# SOM_Power.net
KiCad netlist of a schematic drawn in Altium Designer
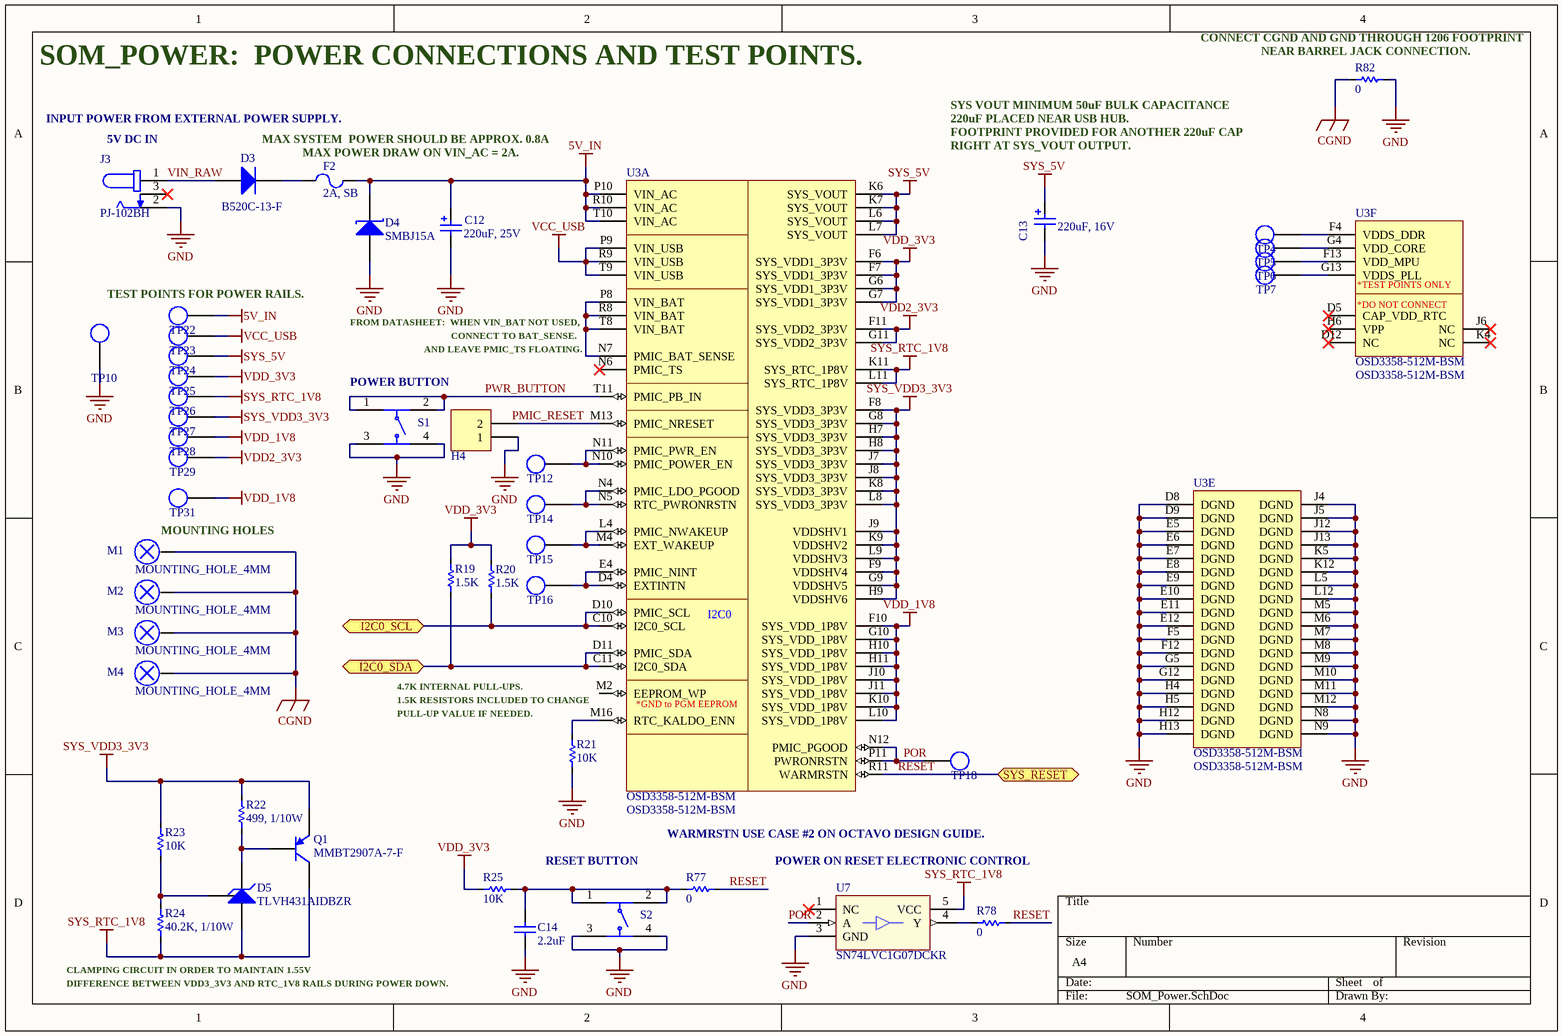
[diagram p0: SOM_Power.SchDoc]

(export (version "E")
  (design (tool "Eeschema 10.0.6"))
  (components
    (comp (ref "C12")
      (value "220uF, 25V")
      (footprint "CAP_SMD_6.3x7.7")
      (description "CAP ALUM 220UF 20% 25V SMD")
      (fields
        (field (name "MANUFACTURER PART NO.") "UCM1E221MCL1GS")
        (field (name "MANUFACTURER") "Nichicon")
      )
      (libsource (lib "OSD335-X_Devboard") (part "UCM1E221MCL1GS"))
    )
    (comp (ref "C13")
      (value "220uF, 16V")
      (footprint "CAP_SMD_6.3x7.7")
      (description "CAP 220 UF 20% 16 V")
      (fields
        (field (name "MANUFACTURER PART NO.") "865080345012")
        (field (name "MANUFACTURER") "Wurth Elektronik")
      )
      (libsource (lib "OSD335-X_Devboard") (part "865080345012"))
    )
    (comp (ref "C14")
      (value "2.2uF")
      (footprint "CAP_0603")
      (description "CAP CER 2.2UF 16V X5R 0603")
      (fields (field (name "MANUFACTURER") "KEMET") (field (name "MANUFACTURER PART NO.") "C0603C104M4RACTU"))
      (libsource (lib "OSD335-X_Devboard") (part "C0603C225M4PAC7867"))
    )
    (comp (ref "D3")
      (value "B520C-13-F")
      (footprint "D0-214AA")
      (description "DIODE SCHOTTKY 20V 5A SMC")
      (fields (field (name "MANUFACTURER") "Diodes Incorporated"))
      (libsource (lib "OSD335-X_Devboard") (part "B520C-13-F"))
    )
    (comp (ref "D4")
      (value "SMBJ15A")
      (footprint "D0-214AA")
      (description "TVS DIODE 15V 24.4V DO214AA")
      (fields (field (name "MANUFACTURER") "Littelfuse Inc."))
      (libsource (lib "OSD335-X_Devboard") (part "SMBJ15A"))
    )
    (comp (ref "D5")
      (value "TLVH431AIDBZR")
      (footprint "SOT-23-3")
      (description "IC VREF SHUNT 18V 1% SOT23-3")
      (fields (field (name "MANUFACTURER") "Texas Instruments"))
      (libsource (lib "OSD335-X_Devboard") (part "TLVH431AIDBZR"))
    )
    (comp (ref "F2")
      (value "2A, SB")
      (footprint "CAP_0603")
      (description "FUSE BOARD MOUNT 2A 32VDC 0603")
      (fields
        (field (name "MANUFACTURER") "Bourns Inc.")
        (field (name "MANUFACTURER PART NO.") "SF-0603S200-2")
      )
      (libsource (lib "OSD335-X_Devboard") (part "SF-0603S200-2"))
    )
    (comp (ref "H4")
      (value "02p")
      (footprint "HEADER_2X1_2.54MM")
      (description "CONN HEADER VERT 2POS 2.54MM")
      (fields
        (field (name "MANUFACTURER") "Wurth Elektronik")
        (field (name "MANUFACTURER PART NO.") "61300211121")
      )
      (libsource (lib "OSD335-X_Devboard") (part "61300211121"))
    )
    (comp (ref "J3")
      (value "PJ-102BH")
      (footprint "PJ-102BH")
      (description "CONN PWR JACK 2.5X5.5MM SOLDER")
      (fields (field (name "MANUFACTURER") "CUI Devices"))
      (libsource (lib "OSD335-X_Devboard") (part "PJ-102BH"))
    )
    (comp (ref "M1")
      (value "MOUNTING_HOLE_4MM")
      (footprint "MOUNTING_HOLE_4MM")
      (libsource (lib "OSD335-X_Devboard") (part "MOUNTING_HOLE_4MM"))
    )
    (comp (ref "M2")
      (value "MOUNTING_HOLE_4MM")
      (footprint "MOUNTING_HOLE_4MM")
      (libsource (lib "OSD335-X_Devboard") (part "MOUNTING_HOLE_4MM"))
    )
    (comp (ref "M3")
      (value "MOUNTING_HOLE_4MM")
      (footprint "MOUNTING_HOLE_4MM")
      (libsource (lib "OSD335-X_Devboard") (part "MOUNTING_HOLE_4MM"))
    )
    (comp (ref "M4")
      (value "MOUNTING_HOLE_4MM")
      (footprint "MOUNTING_HOLE_4MM")
      (libsource (lib "OSD335-X_Devboard") (part "MOUNTING_HOLE_4MM"))
    )
    (comp (ref "Q1")
      (value "MMBT2907A-7-F")
      (footprint "SOT-23-3")
      (description "TRANS PNP 60V 0.6A SOT23-3")
      (fields (field (name "MANUFACTURER") "Diodes Incorporated"))
      (libsource (lib "OSD335-X_Devboard") (part "MMBT2907A"))
    )
    (comp (ref "R19")
      (value "1.5K")
      (footprint "RES_0603")
      (description "RES SMD 1.5K OHM 1% 1/10W 0603")
      (fields (field (name "TOLERANCE") "1%") (field (name "MANUFACTURER") "Yageo"))
      (libsource (lib "OSD335-X_Devboard") (part "RC0603FR-071K5L"))
    )
    (comp (ref "R20")
      (value "1.5K")
      (footprint "RES_0603")
      (description "RES SMD 1.5K OHM 1% 1/10W 0603")
      (fields (field (name "TOLERANCE") "1%") (field (name "MANUFACTURER") "Yageo"))
      (libsource (lib "OSD335-X_Devboard") (part "RC0603FR-071K5L"))
    )
    (comp (ref "R21")
      (value "10K")
      (footprint "RES_0603")
      (description "RES SMD 10K OHM 1% 1/10W 0603")
      (fields (field (name "TOLERANCE") "1%") (field (name "MANUFACTURER") "Yageo"))
      (libsource (lib "OSD335-X_Devboard") (part "RC0603FR-0710KL"))
    )
    (comp (ref "R22")
      (value "499, 1/10W")
      (footprint "RES_0603")
      (description "RES SMD 499 OHM 1% 1/10W 0603")
      (fields (field (name "TOLERANCE") "1%") (field (name "MANUFACTURER") "Yageo"))
      (libsource (lib "OSD335-X_Devboard") (part "RC0603FR-07499RL"))
    )
    (comp (ref "R23")
      (value "10K")
      (footprint "RES_0603")
      (description "RES SMD 10K OHM 1% 1/10W 0603")
      (fields (field (name "TOLERANCE") "1%") (field (name "MANUFACTURER") "Yageo"))
      (libsource (lib "OSD335-X_Devboard") (part "RC0603FR-0710KL"))
    )
    (comp (ref "R24")
      (value "40.2K, 1/10W")
      (footprint "RES_0603")
      (description "RES SMD 40.2K OHM 1% 1/10W 0603")
      (fields (field (name "TOLERANCE") "1%") (field (name "MANUFACTURER") "Yageo"))
      (libsource (lib "OSD335-X_Devboard") (part "RC0603FR-0740K2L"))
    )
    (comp (ref "R25")
      (value "10K")
      (footprint "RES_0603")
      (description "RES SMD 10K OHM 1% 1/10W 0603")
      (fields (field (name "TOLERANCE") "1%") (field (name "MANUFACTURER") "Yageo"))
      (libsource (lib "OSD335-X_Devboard") (part "RC0603FR-0710KL"))
    )
    (comp (ref "R77")
      (value "0")
      (footprint "RES_0603")
      (description "RES SMD 0 OHM JUMPER 1/10W 0603")
      (fields (field (name "MANUFACTURER") "Yageo") (field (name "MANUFACTURER PART NO.") "RC0603JR-070RL"))
      (libsource (lib "OSD335-X_Devboard") (part "RC0603JR-070RL"))
    )
    (comp (ref "R78")
      (value "0")
      (footprint "RES_0603")
      (description "RES SMD 0 OHM JUMPER 1/10W 0603")
      (fields (field (name "MANUFACTURER") "Yageo") (field (name "MANUFACTURER PART NO.") "RC0603JR-070RL"))
      (libsource (lib "OSD335-X_Devboard") (part "RC0603JR-070RL"))
    )
    (comp (ref "R82")
      (value "0")
      (footprint "RES_1206")
      (description "RES 0 OHM JUMPER 1206")
      (fields
        (field (name "MANUFACTURER") "Vishay Dale")
        (field (name "MANUFACTURER PART NO.") "WSL120600000ZEA9")
      )
      (libsource (lib "OSD335-X_Devboard") (part "WSL120600000ZEA9"))
    )
    (comp (ref "S1")
      (value "PTS645SM43SMTR92 LFS")
      (footprint "SWITCH_6x6MM_SMT")
      (description "SWITCH TACTILE SPST-NO 0.05A 12V")
      (fields (field (name "MANUFACTURER") "C&K"))
      (libsource (lib "OSD335-X_Devboard") (part "PTS645SM43SMTR92 LFS"))
    )
    (comp (ref "S2")
      (value "PTS645SM43SMTR92 LFS")
      (footprint "SWITCH_6x6MM_SMT")
      (description "SWITCH TACTILE SPST-NO 0.05A 12V")
      (fields (field (name "MANUFACTURER") "C&K"))
      (libsource (lib "OSD335-X_Devboard") (part "PTS645SM43SMTR92 LFS"))
    )
    (comp (ref "TP4")
      (value "TP_SMD")
      (footprint "TP_SMD")
      (libsource (lib "OSD335-X_Devboard") (part "TP_SMD"))
    )
    (comp (ref "TP5")
      (value "TP_SMD")
      (footprint "TP_SMD")
      (libsource (lib "OSD335-X_Devboard") (part "TP_SMD"))
    )
    (comp (ref "TP6")
      (value "TP_SMD")
      (footprint "TP_SMD")
      (libsource (lib "OSD335-X_Devboard") (part "TP_SMD"))
    )
    (comp (ref "TP7")
      (value "TP_SMD")
      (footprint "TP_SMD")
      (libsource (lib "OSD335-X_Devboard") (part "TP_SMD"))
    )
    (comp (ref "TP10")
      (value "TP_SMD")
      (footprint "TP_SMD")
      (libsource (lib "OSD335-X_Devboard") (part "TP_SMD"))
    )
    (comp (ref "TP12")
      (value "TP_SMD")
      (footprint "TP_SMD")
      (libsource (lib "OSD335-X_Devboard") (part "TP_SMD"))
    )
    (comp (ref "TP14")
      (value "TP_SMD")
      (footprint "TP_SMD")
      (libsource (lib "OSD335-X_Devboard") (part "TP_SMD"))
    )
    (comp (ref "TP15")
      (value "TP_SMD")
      (footprint "TP_SMD")
      (libsource (lib "OSD335-X_Devboard") (part "TP_SMD"))
    )
    (comp (ref "TP16")
      (value "TP_SMD")
      (footprint "TP_SMD")
      (libsource (lib "OSD335-X_Devboard") (part "TP_SMD"))
    )
    (comp (ref "TP18")
      (value "TP_SMD")
      (footprint "TP_SMD")
      (libsource (lib "OSD335-X_Devboard") (part "TP_SMD"))
    )
    (comp (ref "TP22")
      (value "TP_SMD")
      (footprint "TP_SMD")
      (libsource (lib "OSD335-X_Devboard") (part "TP_SMD"))
    )
    (comp (ref "TP23")
      (value "TP_SMD")
      (footprint "TP_SMD")
      (libsource (lib "OSD335-X_Devboard") (part "TP_SMD"))
    )
    (comp (ref "TP24")
      (value "TP_SMD")
      (footprint "TP_SMD")
      (libsource (lib "OSD335-X_Devboard") (part "TP_SMD"))
    )
    (comp (ref "TP25")
      (value "TP_SMD")
      (footprint "TP_SMD")
      (libsource (lib "OSD335-X_Devboard") (part "TP_SMD"))
    )
    (comp (ref "TP26")
      (value "TP_SMD")
      (footprint "TP_SMD")
      (libsource (lib "OSD335-X_Devboard") (part "TP_SMD"))
    )
    (comp (ref "TP27")
      (value "TP_SMD")
      (footprint "TP_SMD")
      (libsource (lib "OSD335-X_Devboard") (part "TP_SMD"))
    )
    (comp (ref "TP28")
      (value "TP_SMD")
      (footprint "TP_SMD")
      (libsource (lib "OSD335-X_Devboard") (part "TP_SMD"))
    )
    (comp (ref "TP29")
      (value "TP_SMD")
      (footprint "TP_SMD")
      (libsource (lib "OSD335-X_Devboard") (part "TP_SMD"))
    )
    (comp (ref "TP31")
      (value "TP_SMD")
      (footprint "TP_SMD")
      (libsource (lib "OSD335-X_Devboard") (part "TP_SMD"))
    )
    (comp (ref "U3")
      (value "OSD3358-512M-BSM")
      (footprint "BGA256C127P16X16_2100X2100X308")
      (description "OSD3358-512M-BSM , 256-FBGA, 21mmx21mmx3mm")
      (fields (field (name "MANUFACTURER") "Octavo Systems") (field (name "PARTNUMBER") "OSD3358-512M-BSM"))
      (libsource (lib "OSD335-X_Devboard") (part "SOM-OSD3358-512M-BSM"))
    )
    (comp (ref "U7")
      (value "SN74LVC1G07DCKR")
      (footprint "SC70")
      (description "IC BUF NON-INVERT 5.5V SC70-5")
      (fields (field (name "MANUFACTURER") "Texas Instruments"))
      (libsource (lib "OSD335-X_Devboard") (part "SN74LVC1G07DCKR"))
    )
  )
  (nets
    (net (code "1") (name "/I2C0_SCL") (class "Default")
      (node (ref "R20") (pin "1") (pinfunction "1_1") (pintype "passive"))
      (node (ref "U3") (pin "C10") (pinfunction "I2C0_SCL_C10") (pintype "bidirectional"))
      (node (ref "U3") (pin "D10") (pinfunction "PMIC_SCL_D10") (pintype "bidirectional"))
    )
    (net (code "2") (name "/I2C0_SDA") (class "Default")
      (node (ref "R19") (pin "1") (pinfunction "1_1") (pintype "passive"))
      (node (ref "U3") (pin "C11") (pinfunction "I2C0_SDA_C11") (pintype "bidirectional"))
      (node (ref "U3") (pin "D11") (pinfunction "PMIC_SDA_D11") (pintype "bidirectional"))
    )
    (net (code "3") (name "/PMIC_RESET") (class "Default")
      (node (ref "H4") (pin "2") (pinfunction "2_2") (pintype "passive"))
      (node (ref "U3") (pin "M13") (pinfunction "PMIC_NRESET_M13") (pintype "bidirectional"))
    )
    (net (code "4") (name "/POR") (class "Default")
      (node (ref "TP18") (pin "1") (pinfunction "1_1") (pintype "passive"))
      (node (ref "U3") (pin "N12") (pinfunction "PMIC_PGOOD_N12") (pintype "bidirectional"))
      (node (ref "U3") (pin "P11") (pinfunction "PWRONRSTN_P11") (pintype "bidirectional"))
      (node (ref "U7") (pin "2") (pinfunction "A_2") (pintype "input"))
    )
    (net (code "5") (name "/PWR_BUTTON") (class "Default")
      (node (ref "S1") (pin "1") (pinfunction "1_1") (pintype "passive"))
      (node (ref "S1") (pin "2") (pinfunction "2_2") (pintype "passive"))
      (node (ref "U3") (pin "T11") (pinfunction "PMIC_PB_IN_T11") (pintype "bidirectional"))
    )
    (net (code "6") (name "/RESET") (class "Default")
      (node (ref "R77") (pin "2") (pinfunction "2_2") (pintype "passive"))
      (node (ref "R78") (pin "2") (pinfunction "2_2") (pintype "passive"))
      (node (ref "U3") (pin "R11") (pinfunction "WARMRSTN_R11") (pintype "bidirectional"))
    )
    (net (code "7") (name "/VIN_RAW") (class "Default")
      (node (ref "D3") (pin "1") (pinfunction "A_1") (pintype "passive"))
      (node (ref "J3") (pin "1") (pinfunction "1_1") (pintype "passive"))
    )
    (net (code "8") (name "5V_IN") (class "Default")
      (node (ref "C12") (pin "2") (pinfunction "P_2") (pintype "passive"))
      (node (ref "D4") (pin "2") (pinfunction "K_2") (pintype "passive"))
      (node (ref "F2") (pin "2") (pinfunction "2_2") (pintype "passive"))
      (node (ref "TP22") (pin "1") (pinfunction "1_1") (pintype "passive"))
      (node (ref "U3") (pin "P10") (pinfunction "VIN_AC_P10") (pintype "power_in"))
      (node (ref "U3") (pin "R10") (pinfunction "VIN_AC_R10") (pintype "power_in"))
      (node (ref "U3") (pin "T10") (pinfunction "VIN_AC_T10") (pintype "power_in"))
    )
    (net (code "9") (name "CGND") (class "Default")
      (node (ref "M1") (pin "1") (pinfunction "1_1") (pintype "passive"))
      (node (ref "M2") (pin "1") (pinfunction "1_1") (pintype "passive"))
      (node (ref "M3") (pin "1") (pinfunction "1_1") (pintype "passive"))
      (node (ref "M4") (pin "1") (pinfunction "1_1") (pintype "passive"))
      (node (ref "R82") (pin "1") (pinfunction "1_1") (pintype "passive"))
    )
    (net (code "10") (name "GND") (class "Default")
      (node (ref "C12") (pin "1") (pinfunction "N_1") (pintype "passive"))
      (node (ref "C13") (pin "1") (pinfunction "N_1") (pintype "passive"))
      (node (ref "C14") (pin "1") (pinfunction "1_1") (pintype "passive"))
      (node (ref "D4") (pin "1") (pinfunction "A_1") (pintype "passive"))
      (node (ref "H4") (pin "1") (pinfunction "1_1") (pintype "passive"))
      (node (ref "J3") (pin "2") (pinfunction "2_2") (pintype "passive"))
      (node (ref "R21") (pin "1") (pinfunction "1_1") (pintype "passive"))
      (node (ref "R82") (pin "2") (pinfunction "2_2") (pintype "passive"))
      (node (ref "S1") (pin "3") (pinfunction "3_3") (pintype "passive"))
      (node (ref "S1") (pin "4") (pinfunction "4_4") (pintype "passive"))
      (node (ref "S2") (pin "3") (pinfunction "3_3") (pintype "passive"))
      (node (ref "S2") (pin "4") (pinfunction "4_4") (pintype "passive"))
      (node (ref "TP10") (pin "1") (pinfunction "1_1") (pintype "passive"))
      (node (ref "U3") (pin "D8") (pinfunction "DGND_D8") (pintype "power_in"))
      (node (ref "U3") (pin "D9") (pinfunction "DGND_D9") (pintype "power_in"))
      (node (ref "U3") (pin "E10") (pinfunction "DGND_E10") (pintype "power_in"))
      (node (ref "U3") (pin "E11") (pinfunction "DGND_E11") (pintype "power_in"))
      (node (ref "U3") (pin "E12") (pinfunction "DGND_E12") (pintype "power_in"))
      (node (ref "U3") (pin "E5") (pinfunction "DGND_E5") (pintype "power_in"))
      (node (ref "U3") (pin "E6") (pinfunction "DGND_E6") (pintype "power_in"))
      (node (ref "U3") (pin "E7") (pinfunction "DGND_E7") (pintype "power_in"))
      (node (ref "U3") (pin "E8") (pinfunction "DGND_E8") (pintype "power_in"))
      (node (ref "U3") (pin "E9") (pinfunction "DGND_E9") (pintype "power_in"))
      (node (ref "U3") (pin "F12") (pinfunction "DGND_F12") (pintype "power_in"))
      (node (ref "U3") (pin "F5") (pinfunction "DGND_F5") (pintype "power_in"))
      (node (ref "U3") (pin "G12") (pinfunction "DGND_G12") (pintype "power_in"))
      (node (ref "U3") (pin "G5") (pinfunction "DGND_G5") (pintype "power_in"))
      (node (ref "U3") (pin "H12") (pinfunction "DGND_H12") (pintype "power_in"))
      (node (ref "U3") (pin "H13") (pinfunction "DGND_H13") (pintype "power_in"))
      (node (ref "U3") (pin "H4") (pinfunction "DGND_H4") (pintype "power_in"))
      (node (ref "U3") (pin "H5") (pinfunction "DGND_H5") (pintype "power_in"))
      (node (ref "U3") (pin "J12") (pinfunction "DGND_J12") (pintype "power_in"))
      (node (ref "U3") (pin "J13") (pinfunction "DGND_J13") (pintype "power_in"))
      (node (ref "U3") (pin "J4") (pinfunction "DGND_J4") (pintype "power_in"))
      (node (ref "U3") (pin "J5") (pinfunction "DGND_J5") (pintype "power_in"))
      (node (ref "U3") (pin "K12") (pinfunction "DGND_K12") (pintype "power_in"))
      (node (ref "U3") (pin "K5") (pinfunction "DGND_K5") (pintype "power_in"))
      (node (ref "U3") (pin "L12") (pinfunction "DGND_L12") (pintype "power_in"))
      (node (ref "U3") (pin "L5") (pinfunction "DGND_L5") (pintype "power_in"))
      (node (ref "U3") (pin "M10") (pinfunction "DGND_M10") (pintype "power_in"))
      (node (ref "U3") (pin "M11") (pinfunction "DGND_M11") (pintype "power_in"))
      (node (ref "U3") (pin "M12") (pinfunction "DGND_M12") (pintype "power_in"))
      (node (ref "U3") (pin "M5") (pinfunction "DGND_M5") (pintype "power_in"))
      (node (ref "U3") (pin "M6") (pinfunction "DGND_M6") (pintype "power_in"))
      (node (ref "U3") (pin "M7") (pinfunction "DGND_M7") (pintype "power_in"))
      (node (ref "U3") (pin "M8") (pinfunction "DGND_M8") (pintype "power_in"))
      (node (ref "U3") (pin "M9") (pinfunction "DGND_M9") (pintype "power_in"))
      (node (ref "U3") (pin "N8") (pinfunction "DGND_N8") (pintype "power_in"))
      (node (ref "U3") (pin "N9") (pinfunction "DGND_N9") (pintype "power_in"))
      (node (ref "U7") (pin "3") (pinfunction "GND_3") (pintype "power_in"))
    )
    (net (code "11") (name "Net-(C14-Pad2)") (class "Default")
      (node (ref "C14") (pin "2") (pinfunction "2_2") (pintype "passive"))
      (node (ref "R25") (pin "1") (pinfunction "1_1") (pintype "passive"))
      (node (ref "R77") (pin "1") (pinfunction "1_1") (pintype "passive"))
      (node (ref "S2") (pin "1") (pinfunction "1_1") (pintype "passive"))
      (node (ref "S2") (pin "2") (pinfunction "2_2") (pintype "passive"))
    )
    (net (code "12") (name "Net-(D3-K)") (class "Default")
      (node (ref "D3") (pin "2") (pinfunction "K_2") (pintype "passive"))
      (node (ref "F2") (pin "1") (pinfunction "1_1") (pintype "passive"))
    )
    (net (code "13") (name "Net-(D5-C)") (class "Default")
      (node (ref "D5") (pin "1") (pinfunction "C_1") (pintype "passive"))
      (node (ref "Q1") (pin "1") (pinfunction "B_1") (pintype "passive"))
      (node (ref "R22") (pin "1") (pinfunction "1_1") (pintype "passive"))
    )
    (net (code "14") (name "Net-(D5-REF)") (class "Default")
      (node (ref "D5") (pin "2") (pinfunction "REF_2") (pintype "passive"))
      (node (ref "R23") (pin "1") (pinfunction "1_1") (pintype "passive"))
      (node (ref "R24") (pin "2") (pinfunction "2_2") (pintype "passive"))
    )
    (net (code "15") (name "Net-(U3A-EXTINTN)") (class "Default")
      (node (ref "TP16") (pin "1") (pinfunction "1_1") (pintype "passive"))
      (node (ref "U3") (pin "D4") (pinfunction "EXTINTN_D4") (pintype "bidirectional"))
      (node (ref "U3") (pin "E4") (pinfunction "PMIC_NINT_E4") (pintype "bidirectional"))
    )
    (net (code "16") (name "Net-(U3A-EXT_WAKEUP)") (class "Default")
      (node (ref "TP15") (pin "1") (pinfunction "1_1") (pintype "passive"))
      (node (ref "U3") (pin "L4") (pinfunction "PMIC_NWAKEUP_L4") (pintype "bidirectional"))
      (node (ref "U3") (pin "M4") (pinfunction "EXT_WAKEUP_M4") (pintype "bidirectional"))
    )
    (net (code "17") (name "Net-(U3A-PMIC_BAT_SENSE)") (class "Default")
      (node (ref "U3") (pin "N7") (pinfunction "PMIC_BAT_SENSE_N7") (pintype "passive"))
      (node (ref "U3") (pin "P8") (pinfunction "VIN_BAT_P8") (pintype "power_in"))
      (node (ref "U3") (pin "R8") (pinfunction "VIN_BAT_R8") (pintype "power_in"))
      (node (ref "U3") (pin "T8") (pinfunction "VIN_BAT_T8") (pintype "power_in"))
    )
    (net (code "18") (name "Net-(U3A-PMIC_LDO_PGOOD)") (class "Default")
      (node (ref "TP14") (pin "1") (pinfunction "1_1") (pintype "passive"))
      (node (ref "U3") (pin "N4") (pinfunction "PMIC_LDO_PGOOD_N4") (pintype "bidirectional"))
      (node (ref "U3") (pin "N5") (pinfunction "RTC_PWRONRSTN_N5") (pintype "bidirectional"))
    )
    (net (code "19") (name "Net-(U3A-PMIC_POWER_EN)") (class "Default")
      (node (ref "TP12") (pin "1") (pinfunction "1_1") (pintype "passive"))
      (node (ref "U3") (pin "N10") (pinfunction "PMIC_POWER_EN_N10") (pintype "bidirectional"))
      (node (ref "U3") (pin "N11") (pinfunction "PMIC_PWR_EN_N11") (pintype "bidirectional"))
    )
    (net (code "20") (name "Net-(U3A-RTC_KALDO_ENN)") (class "Default")
      (node (ref "R21") (pin "2") (pinfunction "2_2") (pintype "passive"))
      (node (ref "U3") (pin "M16") (pinfunction "RTC_KALDO_ENN_M16") (pintype "bidirectional"))
    )
    (net (code "21") (name "Net-(U3F-VDDS_DDR)") (class "Default")
      (node (ref "TP4") (pin "1") (pinfunction "1_1") (pintype "passive"))
      (node (ref "U3") (pin "F4") (pinfunction "VDDS_DDR_F4") (pintype "power_in"))
    )
    (net (code "22") (name "Net-(U3F-VDDS_PLL)") (class "Default")
      (node (ref "TP7") (pin "1") (pinfunction "1_1") (pintype "passive"))
      (node (ref "U3") (pin "G13") (pinfunction "VDDS_PLL_G13") (pintype "power_in"))
    )
    (net (code "23") (name "Net-(U3F-VDD_CORE)") (class "Default")
      (node (ref "TP5") (pin "1") (pinfunction "1_1") (pintype "passive"))
      (node (ref "U3") (pin "G4") (pinfunction "VDD_CORE_G4") (pintype "power_in"))
    )
    (net (code "24") (name "Net-(U3F-VDD_MPU)") (class "Default")
      (node (ref "TP6") (pin "1") (pinfunction "1_1") (pintype "passive"))
      (node (ref "U3") (pin "F13") (pinfunction "VDD_MPU_F13") (pintype "power_in"))
    )
    (net (code "25") (name "Net-(U7-Y)") (class "Default")
      (node (ref "R78") (pin "1") (pinfunction "1_1") (pintype "passive"))
      (node (ref "U7") (pin "4") (pinfunction "Y_4") (pintype "output"))
    )
    (net (code "26") (name "SYS_5V") (class "Default")
      (node (ref "C13") (pin "2") (pinfunction "P_2") (pintype "passive"))
      (node (ref "TP24") (pin "1") (pinfunction "1_1") (pintype "passive"))
      (node (ref "U3") (pin "K6") (pinfunction "SYS_VOUT_K6") (pintype "power_in"))
      (node (ref "U3") (pin "K7") (pinfunction "SYS_VOUT_K7") (pintype "power_in"))
      (node (ref "U3") (pin "L6") (pinfunction "SYS_VOUT_L6") (pintype "power_in"))
      (node (ref "U3") (pin "L7") (pinfunction "SYS_VOUT_L7") (pintype "power_in"))
    )
    (net (code "27") (name "SYS_RTC_1V8") (class "Default")
      (node (ref "D5") (pin "3") (pinfunction "A_3") (pintype "passive"))
      (node (ref "Q1") (pin "3") (pinfunction "C_3") (pintype "passive"))
      (node (ref "R24") (pin "1") (pinfunction "1_1") (pintype "passive"))
      (node (ref "TP26") (pin "1") (pinfunction "1_1") (pintype "passive"))
      (node (ref "U3") (pin "K11") (pinfunction "SYS_RTC_1P8V_K11") (pintype "power_in"))
      (node (ref "U3") (pin "L11") (pinfunction "SYS_RTC_1P8V_L11") (pintype "power_in"))
      (node (ref "U7") (pin "5") (pinfunction "VCC_5") (pintype "power_in"))
    )
    (net (code "28") (name "SYS_VDD3_3V3") (class "Default")
      (node (ref "Q1") (pin "2") (pinfunction "E_2") (pintype "passive"))
      (node (ref "R22") (pin "2") (pinfunction "2_2") (pintype "passive"))
      (node (ref "R23") (pin "2") (pinfunction "2_2") (pintype "passive"))
      (node (ref "TP27") (pin "1") (pinfunction "1_1") (pintype "passive"))
      (node (ref "U3") (pin "F8") (pinfunction "SYS_VDD3_3P3V_F8") (pintype "power_in"))
      (node (ref "U3") (pin "F9") (pinfunction "VDDSHV4_F9") (pintype "power_in"))
      (node (ref "U3") (pin "G8") (pinfunction "SYS_VDD3_3P3V_G8") (pintype "power_in"))
      (node (ref "U3") (pin "G9") (pinfunction "VDDSHV5_G9") (pintype "power_in"))
      (node (ref "U3") (pin "H7") (pinfunction "SYS_VDD3_3P3V_H7") (pintype "power_in"))
      (node (ref "U3") (pin "H8") (pinfunction "SYS_VDD3_3P3V_H8") (pintype "power_in"))
      (node (ref "U3") (pin "H9") (pinfunction "VDDSHV6_H9") (pintype "power_in"))
      (node (ref "U3") (pin "J7") (pinfunction "SYS_VDD3_3P3V_J7") (pintype "power_in"))
      (node (ref "U3") (pin "J8") (pinfunction "SYS_VDD3_3P3V_J8") (pintype "power_in"))
      (node (ref "U3") (pin "J9") (pinfunction "VDDSHV1_J9") (pintype "power_in"))
      (node (ref "U3") (pin "K8") (pinfunction "SYS_VDD3_3P3V_K8") (pintype "power_in"))
      (node (ref "U3") (pin "K9") (pinfunction "VDDSHV2_K9") (pintype "power_in"))
      (node (ref "U3") (pin "L8") (pinfunction "SYS_VDD3_3P3V_L8") (pintype "power_in"))
      (node (ref "U3") (pin "L9") (pinfunction "VDDSHV3_L9") (pintype "power_in"))
    )
    (net (code "29") (name "VCC_USB") (class "Default")
      (node (ref "TP23") (pin "1") (pinfunction "1_1") (pintype "passive"))
      (node (ref "U3") (pin "P9") (pinfunction "VIN_USB_P9") (pintype "power_in"))
      (node (ref "U3") (pin "R9") (pinfunction "VIN_USB_R9") (pintype "power_in"))
      (node (ref "U3") (pin "T9") (pinfunction "VIN_USB_T9") (pintype "power_in"))
    )
    (net (code "30") (name "VDD2_3V3") (class "Default")
      (node (ref "TP29") (pin "1") (pinfunction "1_1") (pintype "passive"))
      (node (ref "U3") (pin "F11") (pinfunction "SYS_VDD2_3P3V_F11") (pintype "power_in"))
      (node (ref "U3") (pin "G11") (pinfunction "SYS_VDD2_3P3V_G11") (pintype "power_in"))
    )
    (net (code "31") (name "VDD_1V8") (class "Default")
      (node (ref "TP28") (pin "1") (pinfunction "1_1") (pintype "passive"))
      (node (ref "TP31") (pin "1") (pinfunction "1_1") (pintype "passive"))
      (node (ref "U3") (pin "F10") (pinfunction "SYS_VDD_1P8V_F10") (pintype "power_in"))
      (node (ref "U3") (pin "G10") (pinfunction "SYS_VDD_1P8V_G10") (pintype "power_in"))
      (node (ref "U3") (pin "H10") (pinfunction "SYS_VDD_1P8V_H10") (pintype "power_in"))
      (node (ref "U3") (pin "H11") (pinfunction "SYS_VDD_1P8V_H11") (pintype "power_in"))
      (node (ref "U3") (pin "J10") (pinfunction "SYS_VDD_1P8V_J10") (pintype "power_in"))
      (node (ref "U3") (pin "J11") (pinfunction "SYS_VDD_1P8V_J11") (pintype "power_in"))
      (node (ref "U3") (pin "K10") (pinfunction "SYS_VDD_1P8V_K10") (pintype "power_in"))
      (node (ref "U3") (pin "L10") (pinfunction "SYS_VDD_1P8V_L10") (pintype "power_in"))
    )
    (net (code "32") (name "VDD_3V3") (class "Default")
      (node (ref "R19") (pin "2") (pinfunction "2_2") (pintype "passive"))
      (node (ref "R20") (pin "2") (pinfunction "2_2") (pintype "passive"))
      (node (ref "R25") (pin "2") (pinfunction "2_2") (pintype "passive"))
      (node (ref "TP25") (pin "1") (pinfunction "1_1") (pintype "passive"))
      (node (ref "U3") (pin "F6") (pinfunction "SYS_VDD1_3P3V_F6") (pintype "power_in"))
      (node (ref "U3") (pin "F7") (pinfunction "SYS_VDD1_3P3V_F7") (pintype "power_in"))
      (node (ref "U3") (pin "G6") (pinfunction "SYS_VDD1_3P3V_G6") (pintype "power_in"))
      (node (ref "U3") (pin "G7") (pinfunction "SYS_VDD1_3P3V_G7") (pintype "power_in"))
    )
    (net (code "33") (name "unconnected-(J3-Pad3)") (class "Default")
      (node (ref "J3") (pin "3") (pinfunction "3_3") (pintype "passive+no_connect"))
    )
    (net (code "34") (name "unconnected-(U3A-EEPROM_WP-PadM2)") (class "Default")
      (node (ref "U3") (pin "M2") (pinfunction "EEPROM_WP_M2") (pintype "bidirectional"))
    )
    (net (code "35") (name "unconnected-(U3A-PMIC_TS-PadN6)") (class "Default")
      (node (ref "U3") (pin "N6") (pinfunction "PMIC_TS_N6") (pintype "passive+no_connect"))
    )
    (net (code "36") (name "unconnected-(U3F-CAP_VDD_RTC-PadD5)") (class "Default")
      (node (ref "U3") (pin "D5") (pinfunction "CAP_VDD_RTC_D5") (pintype "power_in+no_connect"))
    )
    (net (code "37") (name "unconnected-(U3F-NC-PadD12)") (class "Default")
      (node (ref "U3") (pin "D12") (pinfunction "NC_D12") (pintype "power_in+no_connect"))
    )
    (net (code "38") (name "unconnected-(U3F-NC-PadJ6)") (class "Default")
      (node (ref "U3") (pin "J6") (pinfunction "NC_J6") (pintype "power_in+no_connect"))
    )
    (net (code "39") (name "unconnected-(U3F-NC-PadK4)") (class "Default")
      (node (ref "U3") (pin "K4") (pinfunction "NC_K4") (pintype "power_in+no_connect"))
    )
    (net (code "40") (name "unconnected-(U3F-VPP-PadH6)") (class "Default")
      (node (ref "U3") (pin "H6") (pinfunction "VPP_H6") (pintype "power_in+no_connect"))
    )
    (net (code "41") (name "unconnected-(U7-NC-Pad1)") (class "Default")
      (node (ref "U7") (pin "1") (pinfunction "NC_1") (pintype "passive+no_connect"))
    )
  )
)
